# Groupe_5_Azzouz_Berger_Bilongo.net
KiCad netlist of a schematic drawn in EAGLE
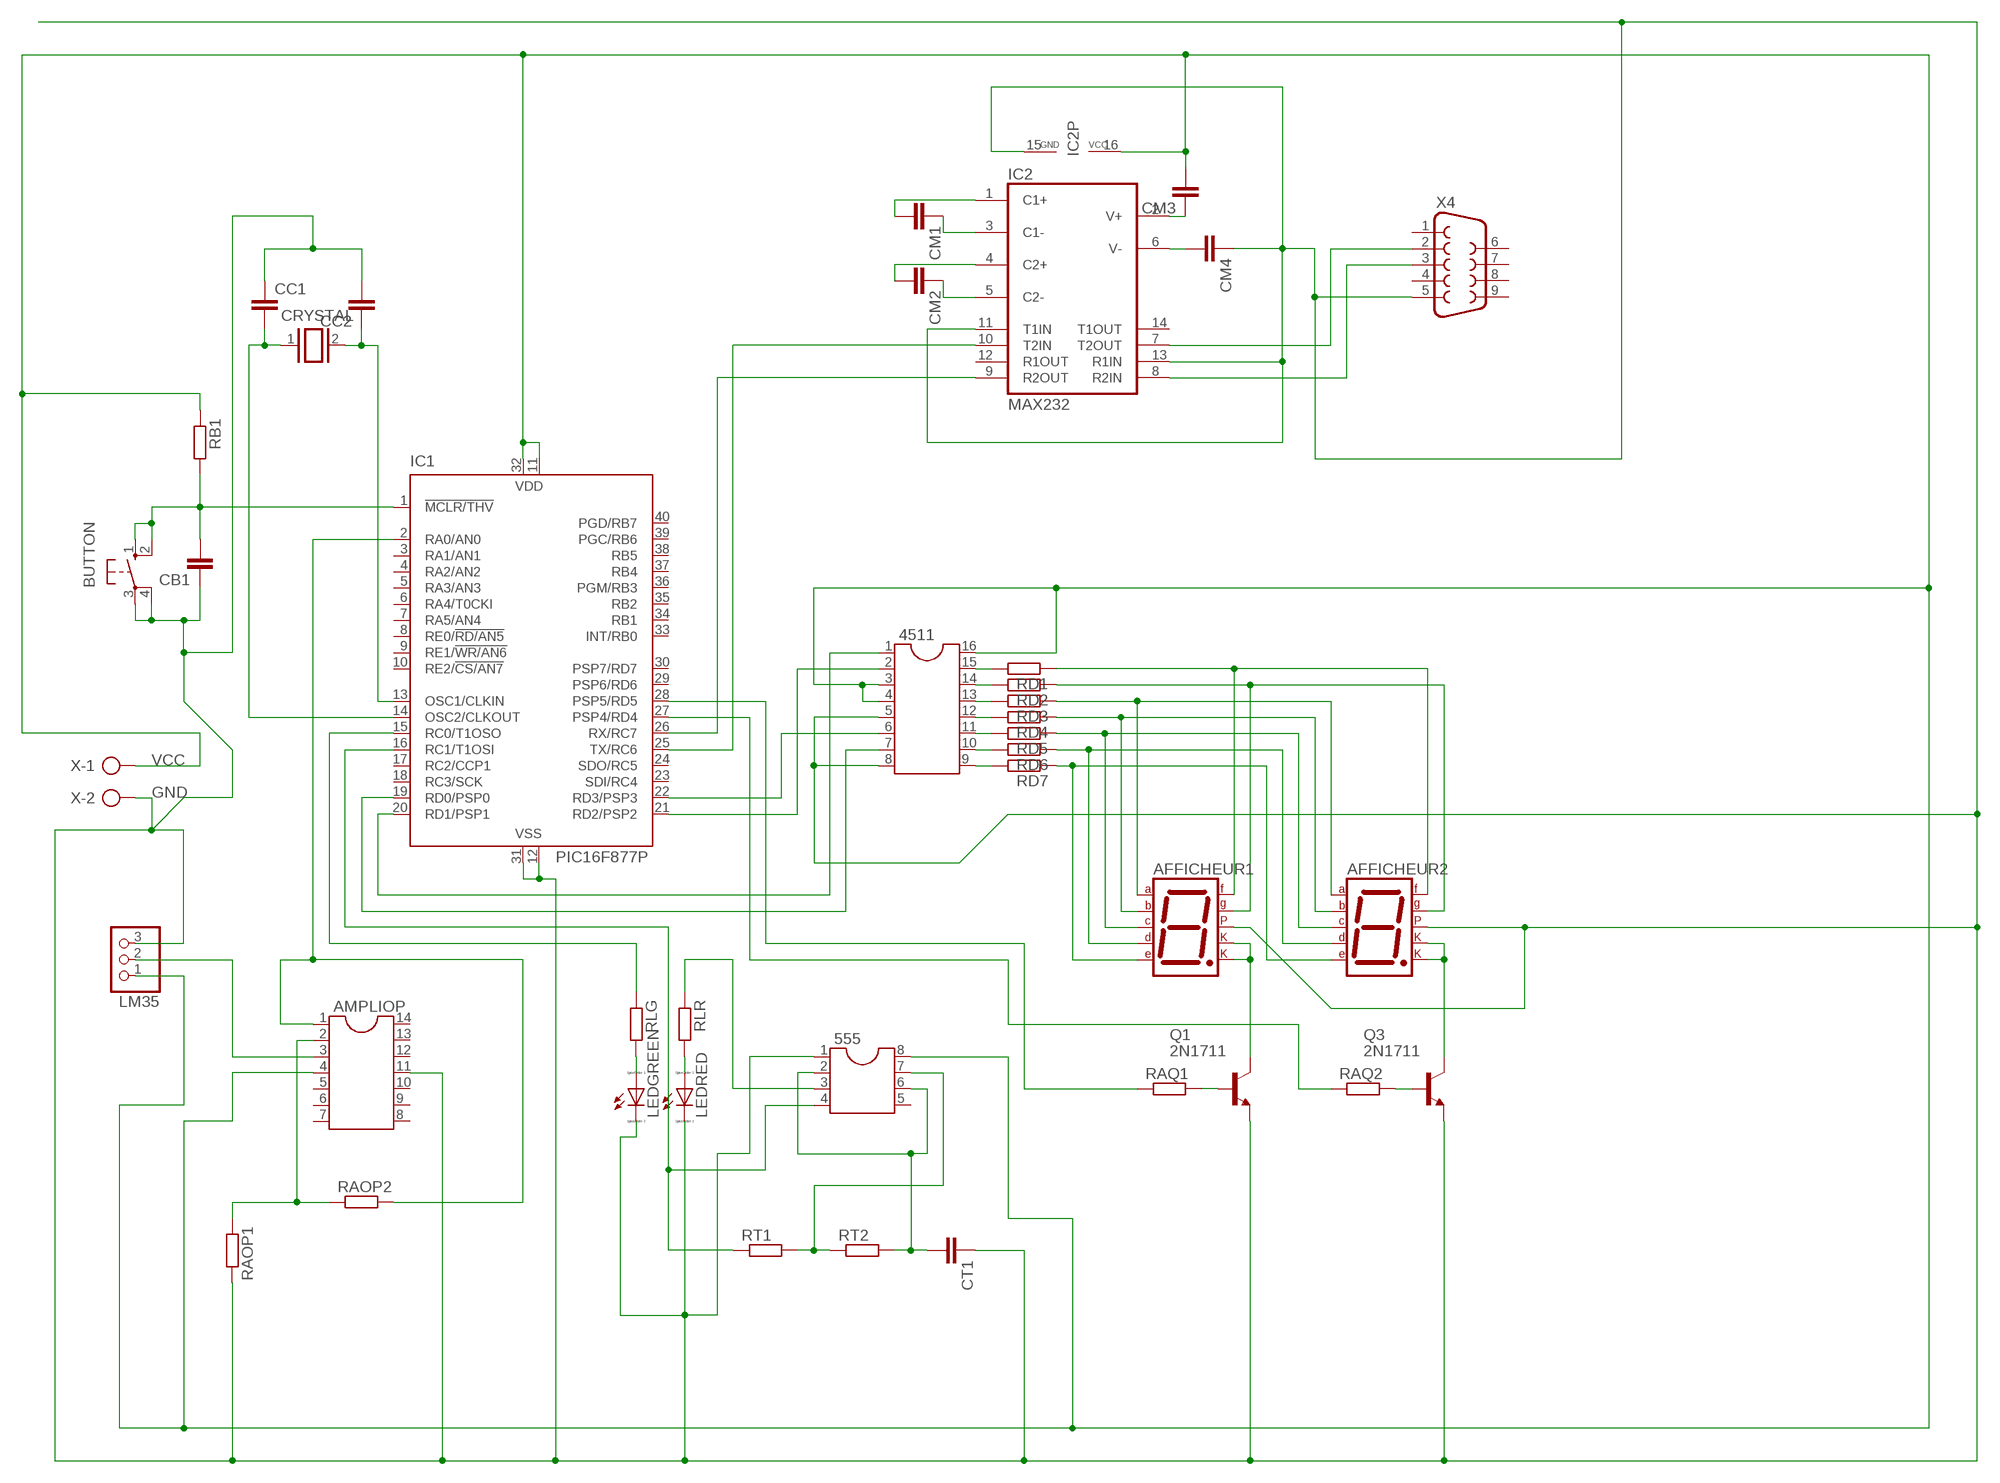
[diagram p0: schematic, sheet 1]

(export (version "E")
  (design (tool "Eeschema 10.0.6"))
  (components
    (comp (ref "555")
      (value "DIL8")
      (footprint "eagle-import:DIL08")
      (libsource (lib "eagle-import") (part "DIL8"))
    )
    (comp (ref "4511")
      (value "DIL16")
      (footprint "eagle-import:DIL16")
      (libsource (lib "eagle-import") (part "DIL16"))
    )
    (comp (ref "AFFICHEUR1")
      (value "7SEG-CK")
      (footprint "eagle-import:7SEG-13")
      (libsource (lib "eagle-import") (part "7SEG-CK"))
    )
    (comp (ref "AFFICHEUR2")
      (value "7SEG-CK")
      (footprint "eagle-import:7SEG-13")
      (libsource (lib "eagle-import") (part "7SEG-CK"))
    )
    (comp (ref "AMPLIOP")
      (value "DIL14")
      (footprint "eagle-import:DIL14")
      (libsource (lib "eagle-import") (part "DIL14"))
    )
    (comp (ref "BUTTON")
      (value "10-XX")
      (footprint "eagle-import:B3F-10XX")
      (fields (field (name "MPN") "B3F-1000"))
      (libsource (lib "eagle-import") (part "10-XX"))
    )
    (comp (ref "CB1")
      (value "C-EU025-050X050")
      (footprint "eagle-import:C025-050X050")
      (libsource (lib "eagle-import") (part "C-EU025-050X050"))
    )
    (comp (ref "CC1")
      (value "C-EU025-050X050")
      (footprint "eagle-import:C025-050X050")
      (libsource (lib "eagle-import") (part "C-EU025-050X050"))
    )
    (comp (ref "CC2")
      (value "C-EU025-050X050")
      (footprint "eagle-import:C025-050X050")
      (libsource (lib "eagle-import") (part "C-EU025-050X050"))
    )
    (comp (ref "CM1")
      (value "C-EU025-050X050")
      (footprint "eagle-import:C025-050X050")
      (libsource (lib "eagle-import") (part "C-EU025-050X050"))
    )
    (comp (ref "CM2")
      (value "C-EU025-050X050")
      (footprint "eagle-import:C025-050X050")
      (libsource (lib "eagle-import") (part "C-EU025-050X050"))
    )
    (comp (ref "CM3")
      (value "C-EU025-050X050")
      (footprint "eagle-import:C025-050X050")
      (libsource (lib "eagle-import") (part "C-EU025-050X050"))
    )
    (comp (ref "CM4")
      (value "C-EU025-050X050")
      (footprint "eagle-import:C025-050X050")
      (libsource (lib "eagle-import") (part "C-EU025-050X050"))
    )
    (comp (ref "CRYSTAL")
      (value "XTAL/S")
      (footprint "eagle-import:QS")
      (libsource (lib "eagle-import") (part "XTAL/S"))
    )
    (comp (ref "CT1")
      (value "C-EU025-050X050")
      (footprint "eagle-import:C025-050X050")
      (libsource (lib "eagle-import") (part "C-EU025-050X050"))
    )
    (comp (ref "IC1")
      (value "PIC16F877P")
      (footprint "eagle-import:DIL40")
      (fields (field (name "MF") "MICROCHIP") (field (name "MPN") "PIC16F877-04/P"))
      (libsource (lib "eagle-import") (part "PIC16F87P7"))
    )
    (comp (ref "IC2")
      (value "MAX232")
      (footprint "eagle-import:DIL16")
      (fields (field (name "MF") "MAXIM") (field (name "MPN") "MAX232ACPE+"))
      (libsource (lib "eagle-import") (part "MAX232"))
    )
    (comp (ref "LEDGREEN")
      (value "LED_ELD260")
      (footprint "eagle-import:LED_LD260")
      (libsource (lib "eagle-import") (part "LED_ELD260"))
    )
    (comp (ref "LEDRED")
      (value "LED_ELD260")
      (footprint "eagle-import:LED_LD260")
      (libsource (lib "eagle-import") (part "LED_ELD260"))
    )
    (comp (ref "LM35")
      (value "PINHD-1X3")
      (footprint "eagle-import:1X03")
      (libsource (lib "eagle-import") (part "PINHD-1X3"))
    )
    (comp (ref "Q1")
      (value "2N1711")
      (footprint "eagle-import:TO39")
      (libsource (lib "eagle-import") (part "2N1711"))
    )
    (comp (ref "Q3")
      (value "2N1711")
      (footprint "eagle-import:TO39")
      (libsource (lib "eagle-import") (part "2N1711"))
    )
    (comp (ref "RAOP1")
      (value "R-EU_0204/7")
      (footprint "eagle-import:0204_7")
      (libsource (lib "eagle-import") (part "R-EU_0204/7"))
    )
    (comp (ref "RAOP2")
      (value "R-EU_0204/7")
      (footprint "eagle-import:0204_7")
      (libsource (lib "eagle-import") (part "R-EU_0204/7"))
    )
    (comp (ref "RAQ1")
      (value "R-EU_0204/7")
      (footprint "eagle-import:0204_7")
      (libsource (lib "eagle-import") (part "R-EU_0204/7"))
    )
    (comp (ref "RAQ2")
      (value "R-EU_0204/7")
      (footprint "eagle-import:0204_7")
      (libsource (lib "eagle-import") (part "R-EU_0204/7"))
    )
    (comp (ref "RB1")
      (value "R-EU_0204/7")
      (footprint "eagle-import:0204_7")
      (libsource (lib "eagle-import") (part "R-EU_0204/7"))
    )
    (comp (ref "RD1")
      (value "R-EU_0204/7")
      (footprint "eagle-import:0204_7")
      (libsource (lib "eagle-import") (part "R-EU_0204/7"))
    )
    (comp (ref "RD2")
      (value "R-EU_0204/7")
      (footprint "eagle-import:0204_7")
      (libsource (lib "eagle-import") (part "R-EU_0204/7"))
    )
    (comp (ref "RD3")
      (value "R-EU_0204/7")
      (footprint "eagle-import:0204_7")
      (libsource (lib "eagle-import") (part "R-EU_0204/7"))
    )
    (comp (ref "RD4")
      (value "R-EU_0204/7")
      (footprint "eagle-import:0204_7")
      (libsource (lib "eagle-import") (part "R-EU_0204/7"))
    )
    (comp (ref "RD5")
      (value "R-EU_0204/7")
      (footprint "eagle-import:0204_7")
      (libsource (lib "eagle-import") (part "R-EU_0204/7"))
    )
    (comp (ref "RD6")
      (value "R-EU_0204/7")
      (footprint "eagle-import:0204_7")
      (libsource (lib "eagle-import") (part "R-EU_0204/7"))
    )
    (comp (ref "RD7")
      (value "R-EU_0204/7")
      (footprint "eagle-import:0204_7")
      (libsource (lib "eagle-import") (part "R-EU_0204/7"))
    )
    (comp (ref "RLG")
      (value "R-EU_0204/7")
      (footprint "eagle-import:0204_7")
      (libsource (lib "eagle-import") (part "R-EU_0204/7"))
    )
    (comp (ref "RLR")
      (value "R-EU_0204/7")
      (footprint "eagle-import:0204_7")
      (libsource (lib "eagle-import") (part "R-EU_0204/7"))
    )
    (comp (ref "RT1")
      (value "R-EU_0204/7")
      (footprint "eagle-import:0204_7")
      (libsource (lib "eagle-import") (part "R-EU_0204/7"))
    )
    (comp (ref "RT2")
      (value "R-EU_0204/7")
      (footprint "eagle-import:0204_7")
      (libsource (lib "eagle-import") (part "R-EU_0204/7"))
    )
    (comp (ref "X")
      (value "AK300/2")
      (footprint "eagle-import:AK300_2")
      (libsource (lib "eagle-import") (part "AK300/2"))
    )
    (comp (ref "X4")
      (value "F09V")
      (footprint "eagle-import:F09V")
      (libsource (lib "eagle-import") (part "F09V"))
    )
  )
  (nets
    (net (code "1") (name "/GND") (class "Default")
      (node (ref "4511") (pin "5") (pinfunction "5_5") (pintype "passive"))
      (node (ref "4511") (pin "8") (pinfunction "8_8") (pintype "passive"))
      (node (ref "555") (pin "1") (pinfunction "1_1") (pintype "passive"))
      (node (ref "AFFICHEUR1") (pin "5") (pinfunction "DP_5") (pintype "passive"))
      (node (ref "AFFICHEUR2") (pin "5") (pinfunction "DP_5") (pintype "passive"))
      (node (ref "AMPLIOP") (pin "11") (pinfunction "11_11") (pintype "passive"))
      (node (ref "BUTTON") (pin "3") (pinfunction "P_3") (pintype "passive"))
      (node (ref "BUTTON") (pin "4") (pinfunction "P1_4") (pintype "passive"))
      (node (ref "CB1") (pin "1") (pinfunction "1_1") (pintype "passive"))
      (node (ref "CC1") (pin "1") (pinfunction "1_1") (pintype "passive"))
      (node (ref "CC2") (pin "2") (pinfunction "2_2") (pintype "passive"))
      (node (ref "CM4") (pin "1") (pinfunction "1_1") (pintype "passive"))
      (node (ref "CT1") (pin "1") (pinfunction "1_1") (pintype "passive"))
      (node (ref "IC1") (pin "12") (pinfunction "VSS_12") (pintype "power_in"))
      (node (ref "IC1") (pin "31") (pinfunction "VSS_31") (pintype "power_in"))
      (node (ref "IC2") (pin "11") (pinfunction "T1IN_11") (pintype "input"))
      (node (ref "IC2") (pin "13") (pinfunction "R1IN_13") (pintype "input"))
      (node (ref "IC2") (pin "15") (pinfunction "GND_15") (pintype "power_in"))
      (node (ref "LEDGREEN") (pin "K") (pinfunction "C_K") (pintype "passive"))
      (node (ref "LEDRED") (pin "K") (pinfunction "C_K") (pintype "passive"))
      (node (ref "LM35") (pin "3") (pinfunction "3_3") (pintype "passive"))
      (node (ref "Q1") (pin "1") (pinfunction "E_1") (pintype "passive"))
      (node (ref "Q3") (pin "1") (pinfunction "E_1") (pintype "passive"))
      (node (ref "RAOP1") (pin "2") (pinfunction "2_2") (pintype "passive"))
      (node (ref "X") (pin "2") (pinfunction "KL_2") (pintype "passive"))
      (node (ref "X4") (pin "5") (pinfunction "5_5") (pintype "passive"))
    )
    (net (code "2") (name "/VCC") (class "Default")
      (node (ref "4511") (pin "16") (pinfunction "16_16") (pintype "passive"))
      (node (ref "4511") (pin "3") (pinfunction "3_3") (pintype "passive"))
      (node (ref "4511") (pin "4") (pinfunction "4_4") (pintype "passive"))
      (node (ref "555") (pin "8") (pinfunction "8_8") (pintype "passive"))
      (node (ref "AMPLIOP") (pin "4") (pinfunction "4_4") (pintype "passive"))
      (node (ref "CM3") (pin "2") (pinfunction "2_2") (pintype "passive"))
      (node (ref "IC1") (pin "11") (pinfunction "VDD_11") (pintype "power_in"))
      (node (ref "IC1") (pin "32") (pinfunction "VDD_32") (pintype "power_in"))
      (node (ref "IC2") (pin "16") (pinfunction "VCC_16") (pintype "power_in"))
      (node (ref "LM35") (pin "1") (pinfunction "1_1") (pintype "passive"))
      (node (ref "RB1") (pin "1") (pinfunction "1_1") (pintype "passive"))
      (node (ref "X") (pin "1") (pinfunction "KL_1") (pintype "passive"))
    )
    (net (code "3") (name "Net-(555-Pad2)") (class "Default")
      (node (ref "555") (pin "2") (pinfunction "2_2") (pintype "passive"))
      (node (ref "555") (pin "6") (pinfunction "6_6") (pintype "passive"))
      (node (ref "CT1") (pin "2") (pinfunction "2_2") (pintype "passive"))
      (node (ref "RT2") (pin "2") (pinfunction "2_2") (pintype "passive"))
    )
    (net (code "4") (name "Net-(555-Pad3)") (class "Default")
      (node (ref "555") (pin "3") (pinfunction "3_3") (pintype "passive"))
      (node (ref "RLR") (pin "1") (pinfunction "1_1") (pintype "passive"))
    )
    (net (code "5") (name "Net-(555-Pad7)") (class "Default")
      (node (ref "555") (pin "7") (pinfunction "7_7") (pintype "passive"))
      (node (ref "RT1") (pin "2") (pinfunction "2_2") (pintype "passive"))
      (node (ref "RT2") (pin "1") (pinfunction "1_1") (pintype "passive"))
    )
    (net (code "6") (name "Net-(4511-Pad9)") (class "Default")
      (node (ref "4511") (pin "9") (pinfunction "9_9") (pintype "passive"))
      (node (ref "RD7") (pin "2") (pinfunction "2_2") (pintype "passive"))
    )
    (net (code "7") (name "Net-(4511-Pad10)") (class "Default")
      (node (ref "4511") (pin "10") (pinfunction "10_10") (pintype "passive"))
      (node (ref "RD6") (pin "2") (pinfunction "2_2") (pintype "passive"))
    )
    (net (code "8") (name "Net-(4511-Pad11)") (class "Default")
      (node (ref "4511") (pin "11") (pinfunction "11_11") (pintype "passive"))
      (node (ref "RD5") (pin "2") (pinfunction "2_2") (pintype "passive"))
    )
    (net (code "9") (name "Net-(4511-Pad12)") (class "Default")
      (node (ref "4511") (pin "12") (pinfunction "12_12") (pintype "passive"))
      (node (ref "RD4") (pin "2") (pinfunction "2_2") (pintype "passive"))
    )
    (net (code "10") (name "Net-(4511-Pad13)") (class "Default")
      (node (ref "4511") (pin "13") (pinfunction "13_13") (pintype "passive"))
      (node (ref "RD3") (pin "2") (pinfunction "2_2") (pintype "passive"))
    )
    (net (code "11") (name "Net-(4511-Pad14)") (class "Default")
      (node (ref "4511") (pin "14") (pinfunction "14_14") (pintype "passive"))
      (node (ref "RD2") (pin "2") (pinfunction "2_2") (pintype "passive"))
    )
    (net (code "12") (name "Net-(4511-Pad15)") (class "Default")
      (node (ref "4511") (pin "15") (pinfunction "15_15") (pintype "passive"))
      (node (ref "RD1") (pin "2") (pinfunction "2_2") (pintype "passive"))
    )
    (net (code "13") (name "Net-(AFFICHEUR1-A)") (class "Default")
      (node (ref "AFFICHEUR1") (pin "7") (pinfunction "A_7") (pintype "passive"))
      (node (ref "AFFICHEUR2") (pin "7") (pinfunction "A_7") (pintype "passive"))
      (node (ref "RD3") (pin "1") (pinfunction "1_1") (pintype "passive"))
    )
    (net (code "14") (name "Net-(AFFICHEUR1-B)") (class "Default")
      (node (ref "AFFICHEUR1") (pin "6") (pinfunction "B_6") (pintype "passive"))
      (node (ref "AFFICHEUR2") (pin "6") (pinfunction "B_6") (pintype "passive"))
      (node (ref "RD4") (pin "1") (pinfunction "1_1") (pintype "passive"))
    )
    (net (code "15") (name "Net-(AFFICHEUR1-C)") (class "Default")
      (node (ref "AFFICHEUR1") (pin "4") (pinfunction "C_4") (pintype "passive"))
      (node (ref "AFFICHEUR2") (pin "4") (pinfunction "C_4") (pintype "passive"))
      (node (ref "RD5") (pin "1") (pinfunction "1_1") (pintype "passive"))
    )
    (net (code "16") (name "Net-(AFFICHEUR1-CK1)") (class "Default")
      (node (ref "AFFICHEUR1") (pin "3") (pinfunction "CK1_3") (pintype "passive"))
      (node (ref "AFFICHEUR1") (pin "8") (pinfunction "CK2_8") (pintype "passive"))
      (node (ref "Q1") (pin "3") (pinfunction "C_3") (pintype "passive"))
    )
    (net (code "17") (name "Net-(AFFICHEUR1-D)") (class "Default")
      (node (ref "AFFICHEUR1") (pin "2") (pinfunction "D_2") (pintype "passive"))
      (node (ref "AFFICHEUR2") (pin "2") (pinfunction "D_2") (pintype "passive"))
      (node (ref "RD6") (pin "1") (pinfunction "1_1") (pintype "passive"))
    )
    (net (code "18") (name "Net-(AFFICHEUR1-E)") (class "Default")
      (node (ref "AFFICHEUR1") (pin "1") (pinfunction "E_1") (pintype "passive"))
      (node (ref "AFFICHEUR2") (pin "1") (pinfunction "E_1") (pintype "passive"))
      (node (ref "RD7") (pin "1") (pinfunction "1_1") (pintype "passive"))
    )
    (net (code "19") (name "Net-(AFFICHEUR1-F)") (class "Default")
      (node (ref "AFFICHEUR1") (pin "9") (pinfunction "F_9") (pintype "passive"))
      (node (ref "AFFICHEUR2") (pin "9") (pinfunction "F_9") (pintype "passive"))
      (node (ref "RD1") (pin "1") (pinfunction "1_1") (pintype "passive"))
    )
    (net (code "20") (name "Net-(AFFICHEUR1-G)") (class "Default")
      (node (ref "AFFICHEUR1") (pin "10") (pinfunction "G_10") (pintype "passive"))
      (node (ref "AFFICHEUR2") (pin "10") (pinfunction "G_10") (pintype "passive"))
      (node (ref "RD2") (pin "1") (pinfunction "1_1") (pintype "passive"))
    )
    (net (code "21") (name "Net-(AFFICHEUR2-CK1)") (class "Default")
      (node (ref "AFFICHEUR2") (pin "3") (pinfunction "CK1_3") (pintype "passive"))
      (node (ref "AFFICHEUR2") (pin "8") (pinfunction "CK2_8") (pintype "passive"))
      (node (ref "Q3") (pin "3") (pinfunction "C_3") (pintype "passive"))
    )
    (net (code "22") (name "Net-(AMPLIOP-Pad2)") (class "Default")
      (node (ref "AMPLIOP") (pin "2") (pinfunction "2_2") (pintype "passive"))
      (node (ref "RAOP1") (pin "1") (pinfunction "1_1") (pintype "passive"))
      (node (ref "RAOP2") (pin "1") (pinfunction "1_1") (pintype "passive"))
    )
    (net (code "23") (name "Net-(AMPLIOP-Pad3)") (class "Default")
      (node (ref "AMPLIOP") (pin "3") (pinfunction "3_3") (pintype "passive"))
      (node (ref "LM35") (pin "2") (pinfunction "2_2") (pintype "passive"))
    )
    (net (code "24") (name "Net-(BUTTON-S)") (class "Default")
      (node (ref "BUTTON") (pin "1") (pinfunction "S_1") (pintype "passive"))
      (node (ref "BUTTON") (pin "2") (pinfunction "S1_2") (pintype "passive"))
      (node (ref "CB1") (pin "2") (pinfunction "2_2") (pintype "passive"))
      (node (ref "IC1") (pin "1") (pinfunction "~{MCLR/THV}_1") (pintype "input"))
      (node (ref "RB1") (pin "2") (pinfunction "2_2") (pintype "passive"))
    )
    (net (code "25") (name "Net-(IC1-OSC1{slash}CLKIN)") (class "Default")
      (node (ref "CC2") (pin "1") (pinfunction "1_1") (pintype "passive"))
      (node (ref "CRYSTAL") (pin "2") (pinfunction "2_2") (pintype "passive"))
      (node (ref "IC1") (pin "13") (pinfunction "OSC1/CLKIN_13") (pintype "input"))
    )
    (net (code "26") (name "Net-(IC1-OSC2{slash}CLKOUT)") (class "Default")
      (node (ref "CC1") (pin "2") (pinfunction "2_2") (pintype "passive"))
      (node (ref "CRYSTAL") (pin "1") (pinfunction "1_1") (pintype "passive"))
      (node (ref "IC1") (pin "14") (pinfunction "OSC2/CLKOUT_14") (pintype "output"))
    )
    (net (code "27") (name "Net-(IC1-PSP4{slash}RD4)") (class "Default")
      (node (ref "IC1") (pin "27") (pinfunction "PSP4/RD4_27") (pintype "bidirectional"))
      (node (ref "RAQ2") (pin "1") (pinfunction "1_1") (pintype "passive"))
    )
    (net (code "28") (name "Net-(IC1-PSP5{slash}RD5)") (class "Default")
      (node (ref "IC1") (pin "28") (pinfunction "PSP5/RD5_28") (pintype "bidirectional"))
      (node (ref "RAQ1") (pin "1") (pinfunction "1_1") (pintype "passive"))
    )
    (net (code "29") (name "Net-(IC1-RA0{slash}AN0)") (class "Default")
      (node (ref "AMPLIOP") (pin "1") (pinfunction "1_1") (pintype "passive"))
      (node (ref "IC1") (pin "2") (pinfunction "RA0/AN0_2") (pintype "bidirectional"))
      (node (ref "RAOP2") (pin "2") (pinfunction "2_2") (pintype "passive"))
    )
    (net (code "30") (name "Net-(IC1-RC0{slash}T1OSO)") (class "Default")
      (node (ref "IC1") (pin "15") (pinfunction "RC0/T1OSO_15") (pintype "bidirectional"))
      (node (ref "RLG") (pin "1") (pinfunction "1_1") (pintype "passive"))
    )
    (net (code "31") (name "Net-(IC1-RC1{slash}T1OSI)") (class "Default")
      (node (ref "555") (pin "4") (pinfunction "4_4") (pintype "passive"))
      (node (ref "IC1") (pin "16") (pinfunction "RC1/T1OSI_16") (pintype "bidirectional"))
      (node (ref "RT1") (pin "1") (pinfunction "1_1") (pintype "passive"))
    )
    (net (code "32") (name "Net-(IC1-RD0{slash}PSP0)") (class "Default")
      (node (ref "4511") (pin "7") (pinfunction "7_7") (pintype "passive"))
      (node (ref "IC1") (pin "19") (pinfunction "RD0/PSP0_19") (pintype "bidirectional"))
    )
    (net (code "33") (name "Net-(IC1-RD1{slash}PSP1)") (class "Default")
      (node (ref "4511") (pin "1") (pinfunction "1_1") (pintype "passive"))
      (node (ref "IC1") (pin "20") (pinfunction "RD1/PSP1_20") (pintype "bidirectional"))
    )
    (net (code "34") (name "Net-(IC1-RD2{slash}PSP2)") (class "Default")
      (node (ref "4511") (pin "2") (pinfunction "2_2") (pintype "passive"))
      (node (ref "IC1") (pin "21") (pinfunction "RD2/PSP2_21") (pintype "bidirectional"))
    )
    (net (code "35") (name "Net-(IC1-RD3{slash}PSP3)") (class "Default")
      (node (ref "4511") (pin "6") (pinfunction "6_6") (pintype "passive"))
      (node (ref "IC1") (pin "22") (pinfunction "RD3/PSP3_22") (pintype "bidirectional"))
    )
    (net (code "36") (name "Net-(IC1-RX{slash}RC7)") (class "Default")
      (node (ref "IC1") (pin "26") (pinfunction "RX/RC7_26") (pintype "bidirectional"))
      (node (ref "IC2") (pin "9") (pinfunction "R2OUT_9") (pintype "output"))
    )
    (net (code "37") (name "Net-(IC1-TX{slash}RC6)") (class "Default")
      (node (ref "IC1") (pin "25") (pinfunction "TX/RC6_25") (pintype "bidirectional"))
      (node (ref "IC2") (pin "10") (pinfunction "T2IN_10") (pintype "input"))
    )
    (net (code "38") (name "Net-(IC2A-C1+)") (class "Default")
      (node (ref "CM1") (pin "2") (pinfunction "2_2") (pintype "passive"))
      (node (ref "IC2") (pin "1") (pinfunction "C1+_1") (pintype "bidirectional"))
    )
    (net (code "39") (name "Net-(IC2A-C1-)") (class "Default")
      (node (ref "CM1") (pin "1") (pinfunction "1_1") (pintype "passive"))
      (node (ref "IC2") (pin "3") (pinfunction "C1-_3") (pintype "bidirectional"))
    )
    (net (code "40") (name "Net-(IC2A-C2+)") (class "Default")
      (node (ref "CM2") (pin "2") (pinfunction "2_2") (pintype "passive"))
      (node (ref "IC2") (pin "4") (pinfunction "C2+_4") (pintype "bidirectional"))
    )
    (net (code "41") (name "Net-(IC2A-C2-)") (class "Default")
      (node (ref "CM2") (pin "1") (pinfunction "1_1") (pintype "passive"))
      (node (ref "IC2") (pin "5") (pinfunction "C2-_5") (pintype "bidirectional"))
    )
    (net (code "42") (name "Net-(IC2A-R2IN)") (class "Default")
      (node (ref "IC2") (pin "8") (pinfunction "R2IN_8") (pintype "input"))
      (node (ref "X4") (pin "3") (pinfunction "3_3") (pintype "passive"))
    )
    (net (code "43") (name "Net-(IC2A-T2OUT)") (class "Default")
      (node (ref "IC2") (pin "7") (pinfunction "T2OUT_7") (pintype "output"))
      (node (ref "X4") (pin "2") (pinfunction "2_2") (pintype "passive"))
    )
    (net (code "44") (name "Net-(IC2A-V+)") (class "Default")
      (node (ref "CM3") (pin "1") (pinfunction "1_1") (pintype "passive"))
      (node (ref "IC2") (pin "2") (pinfunction "V+_2") (pintype "bidirectional"))
    )
    (net (code "45") (name "Net-(IC2A-V-)") (class "Default")
      (node (ref "CM4") (pin "2") (pinfunction "2_2") (pintype "passive"))
      (node (ref "IC2") (pin "6") (pinfunction "V-_6") (pintype "bidirectional"))
    )
    (net (code "46") (name "Net-(LEDGREEN-PadA)") (class "Default")
      (node (ref "LEDGREEN") (pin "A") (pinfunction "A_A") (pintype "passive"))
      (node (ref "RLG") (pin "2") (pinfunction "2_2") (pintype "passive"))
    )
    (net (code "47") (name "Net-(LEDRED-PadA)") (class "Default")
      (node (ref "LEDRED") (pin "A") (pinfunction "A_A") (pintype "passive"))
      (node (ref "RLR") (pin "2") (pinfunction "2_2") (pintype "passive"))
    )
    (net (code "48") (name "Net-(Q1-B)") (class "Default")
      (node (ref "Q1") (pin "2") (pinfunction "B_2") (pintype "passive"))
      (node (ref "RAQ1") (pin "2") (pinfunction "2_2") (pintype "passive"))
    )
    (net (code "49") (name "Net-(Q3-B)") (class "Default")
      (node (ref "Q3") (pin "2") (pinfunction "B_2") (pintype "passive"))
      (node (ref "RAQ2") (pin "2") (pinfunction "2_2") (pintype "passive"))
    )
    (net (code "50") (name "unconnected-(555-Pad5)") (class "Default")
      (node (ref "555") (pin "5") (pinfunction "5_5") (pintype "passive"))
    )
    (net (code "51") (name "unconnected-(AMPLIOP-Pad5)") (class "Default")
      (node (ref "AMPLIOP") (pin "5") (pinfunction "5_5") (pintype "passive"))
    )
    (net (code "52") (name "unconnected-(AMPLIOP-Pad6)") (class "Default")
      (node (ref "AMPLIOP") (pin "6") (pinfunction "6_6") (pintype "passive"))
    )
    (net (code "53") (name "unconnected-(AMPLIOP-Pad7)") (class "Default")
      (node (ref "AMPLIOP") (pin "7") (pinfunction "7_7") (pintype "passive"))
    )
    (net (code "54") (name "unconnected-(AMPLIOP-Pad8)") (class "Default")
      (node (ref "AMPLIOP") (pin "8") (pinfunction "8_8") (pintype "passive"))
    )
    (net (code "55") (name "unconnected-(AMPLIOP-Pad9)") (class "Default")
      (node (ref "AMPLIOP") (pin "9") (pinfunction "9_9") (pintype "passive"))
    )
    (net (code "56") (name "unconnected-(AMPLIOP-Pad10)") (class "Default")
      (node (ref "AMPLIOP") (pin "10") (pinfunction "10_10") (pintype "passive"))
    )
    (net (code "57") (name "unconnected-(AMPLIOP-Pad12)") (class "Default")
      (node (ref "AMPLIOP") (pin "12") (pinfunction "12_12") (pintype "passive"))
    )
    (net (code "58") (name "unconnected-(AMPLIOP-Pad13)") (class "Default")
      (node (ref "AMPLIOP") (pin "13") (pinfunction "13_13") (pintype "passive"))
    )
    (net (code "59") (name "unconnected-(AMPLIOP-Pad14)") (class "Default")
      (node (ref "AMPLIOP") (pin "14") (pinfunction "14_14") (pintype "passive"))
    )
    (net (code "60") (name "unconnected-(IC1-INT{slash}RB0-Pad33)") (class "Default")
      (node (ref "IC1") (pin "33") (pinfunction "INT/RB0_33") (pintype "bidirectional"))
    )
    (net (code "61") (name "unconnected-(IC1-PGC{slash}RB6-Pad39)") (class "Default")
      (node (ref "IC1") (pin "39") (pinfunction "PGC/RB6_39") (pintype "bidirectional"))
    )
    (net (code "62") (name "unconnected-(IC1-PGD{slash}RB7-Pad40)") (class "Default")
      (node (ref "IC1") (pin "40") (pinfunction "PGD/RB7_40") (pintype "bidirectional"))
    )
    (net (code "63") (name "unconnected-(IC1-PGM{slash}RB3-Pad36)") (class "Default")
      (node (ref "IC1") (pin "36") (pinfunction "PGM/RB3_36") (pintype "bidirectional"))
    )
    (net (code "64") (name "unconnected-(IC1-PSP6{slash}RD6-Pad29)") (class "Default")
      (node (ref "IC1") (pin "29") (pinfunction "PSP6/RD6_29") (pintype "bidirectional"))
    )
    (net (code "65") (name "unconnected-(IC1-PSP7{slash}RD7-Pad30)") (class "Default")
      (node (ref "IC1") (pin "30") (pinfunction "PSP7/RD7_30") (pintype "bidirectional"))
    )
    (net (code "66") (name "unconnected-(IC1-RA1{slash}AN1-Pad3)") (class "Default")
      (node (ref "IC1") (pin "3") (pinfunction "RA1/AN1_3") (pintype "bidirectional"))
    )
    (net (code "67") (name "unconnected-(IC1-RA2{slash}AN2-Pad4)") (class "Default")
      (node (ref "IC1") (pin "4") (pinfunction "RA2/AN2_4") (pintype "bidirectional"))
    )
    (net (code "68") (name "unconnected-(IC1-RA3{slash}AN3-Pad5)") (class "Default")
      (node (ref "IC1") (pin "5") (pinfunction "RA3/AN3_5") (pintype "bidirectional"))
    )
    (net (code "69") (name "unconnected-(IC1-RA4{slash}T0CKI-Pad6)") (class "Default")
      (node (ref "IC1") (pin "6") (pinfunction "RA4/T0CKI_6") (pintype "bidirectional"))
    )
    (net (code "70") (name "unconnected-(IC1-RA5{slash}AN4-Pad7)") (class "Default")
      (node (ref "IC1") (pin "7") (pinfunction "RA5/AN4_7") (pintype "bidirectional"))
    )
    (net (code "71") (name "unconnected-(IC1-RB1-Pad34)") (class "Default")
      (node (ref "IC1") (pin "34") (pinfunction "RB1_34") (pintype "bidirectional"))
    )
    (net (code "72") (name "unconnected-(IC1-RB2-Pad35)") (class "Default")
      (node (ref "IC1") (pin "35") (pinfunction "RB2_35") (pintype "bidirectional"))
    )
    (net (code "73") (name "unconnected-(IC1-RB4-Pad37)") (class "Default")
      (node (ref "IC1") (pin "37") (pinfunction "RB4_37") (pintype "bidirectional"))
    )
    (net (code "74") (name "unconnected-(IC1-RB5-Pad38)") (class "Default")
      (node (ref "IC1") (pin "38") (pinfunction "RB5_38") (pintype "bidirectional"))
    )
    (net (code "75") (name "unconnected-(IC1-RC2{slash}CCP1-Pad17)") (class "Default")
      (node (ref "IC1") (pin "17") (pinfunction "RC2/CCP1_17") (pintype "bidirectional"))
    )
    (net (code "76") (name "unconnected-(IC1-RC3{slash}SCK-Pad18)") (class "Default")
      (node (ref "IC1") (pin "18") (pinfunction "RC3/SCK_18") (pintype "bidirectional"))
    )
    (net (code "77") (name "unconnected-(IC1-RE0{slash}~{RD{slash}AN5}-Pad8)") (class "Default")
      (node (ref "IC1") (pin "8") (pinfunction "RE0/~{RD/AN5}_8") (pintype "bidirectional"))
    )
    (net (code "78") (name "unconnected-(IC1-RE1{slash}~{WR{slash}AN6}-Pad9)") (class "Default")
      (node (ref "IC1") (pin "9") (pinfunction "RE1/~{WR/AN6}_9") (pintype "bidirectional"))
    )
    (net (code "79") (name "unconnected-(IC1-RE2{slash}~{CS{slash}AN7}-Pad10)") (class "Default")
      (node (ref "IC1") (pin "10") (pinfunction "RE2/~{CS/AN7}_10") (pintype "bidirectional"))
    )
    (net (code "80") (name "unconnected-(IC1-SDI{slash}RC4-Pad23)") (class "Default")
      (node (ref "IC1") (pin "23") (pinfunction "SDI/RC4_23") (pintype "bidirectional"))
    )
    (net (code "81") (name "unconnected-(IC1-SDO{slash}RC5-Pad24)") (class "Default")
      (node (ref "IC1") (pin "24") (pinfunction "SDO/RC5_24") (pintype "bidirectional"))
    )
    (net (code "82") (name "unconnected-(IC2A-R1OUT-Pad12)") (class "Default")
      (node (ref "IC2") (pin "12") (pinfunction "R1OUT_12") (pintype "output"))
    )
    (net (code "83") (name "unconnected-(IC2A-T1OUT-Pad14)") (class "Default")
      (node (ref "IC2") (pin "14") (pinfunction "T1OUT_14") (pintype "output"))
    )
    (net (code "84") (name "unconnected-(X4-Pad1)") (class "Default")
      (node (ref "X4") (pin "1") (pinfunction "1_1") (pintype "passive"))
    )
    (net (code "85") (name "unconnected-(X4-Pad4)") (class "Default")
      (node (ref "X4") (pin "4") (pinfunction "4_4") (pintype "passive"))
    )
    (net (code "86") (name "unconnected-(X4-Pad6)") (class "Default")
      (node (ref "X4") (pin "6") (pinfunction "6_6") (pintype "passive"))
    )
    (net (code "87") (name "unconnected-(X4-Pad7)") (class "Default")
      (node (ref "X4") (pin "7") (pinfunction "7_7") (pintype "passive"))
    )
    (net (code "88") (name "unconnected-(X4-Pad8)") (class "Default")
      (node (ref "X4") (pin "8") (pinfunction "8_8") (pintype "passive"))
    )
    (net (code "89") (name "unconnected-(X4-Pad9)") (class "Default")
      (node (ref "X4") (pin "9") (pinfunction "9_9") (pintype "passive"))
    )
  )
)
